# TUDSSL_condenar__Hardware_PCBs_Misc_Apo4.net
KiCad netlist of a schematic drawn in Altium Designer
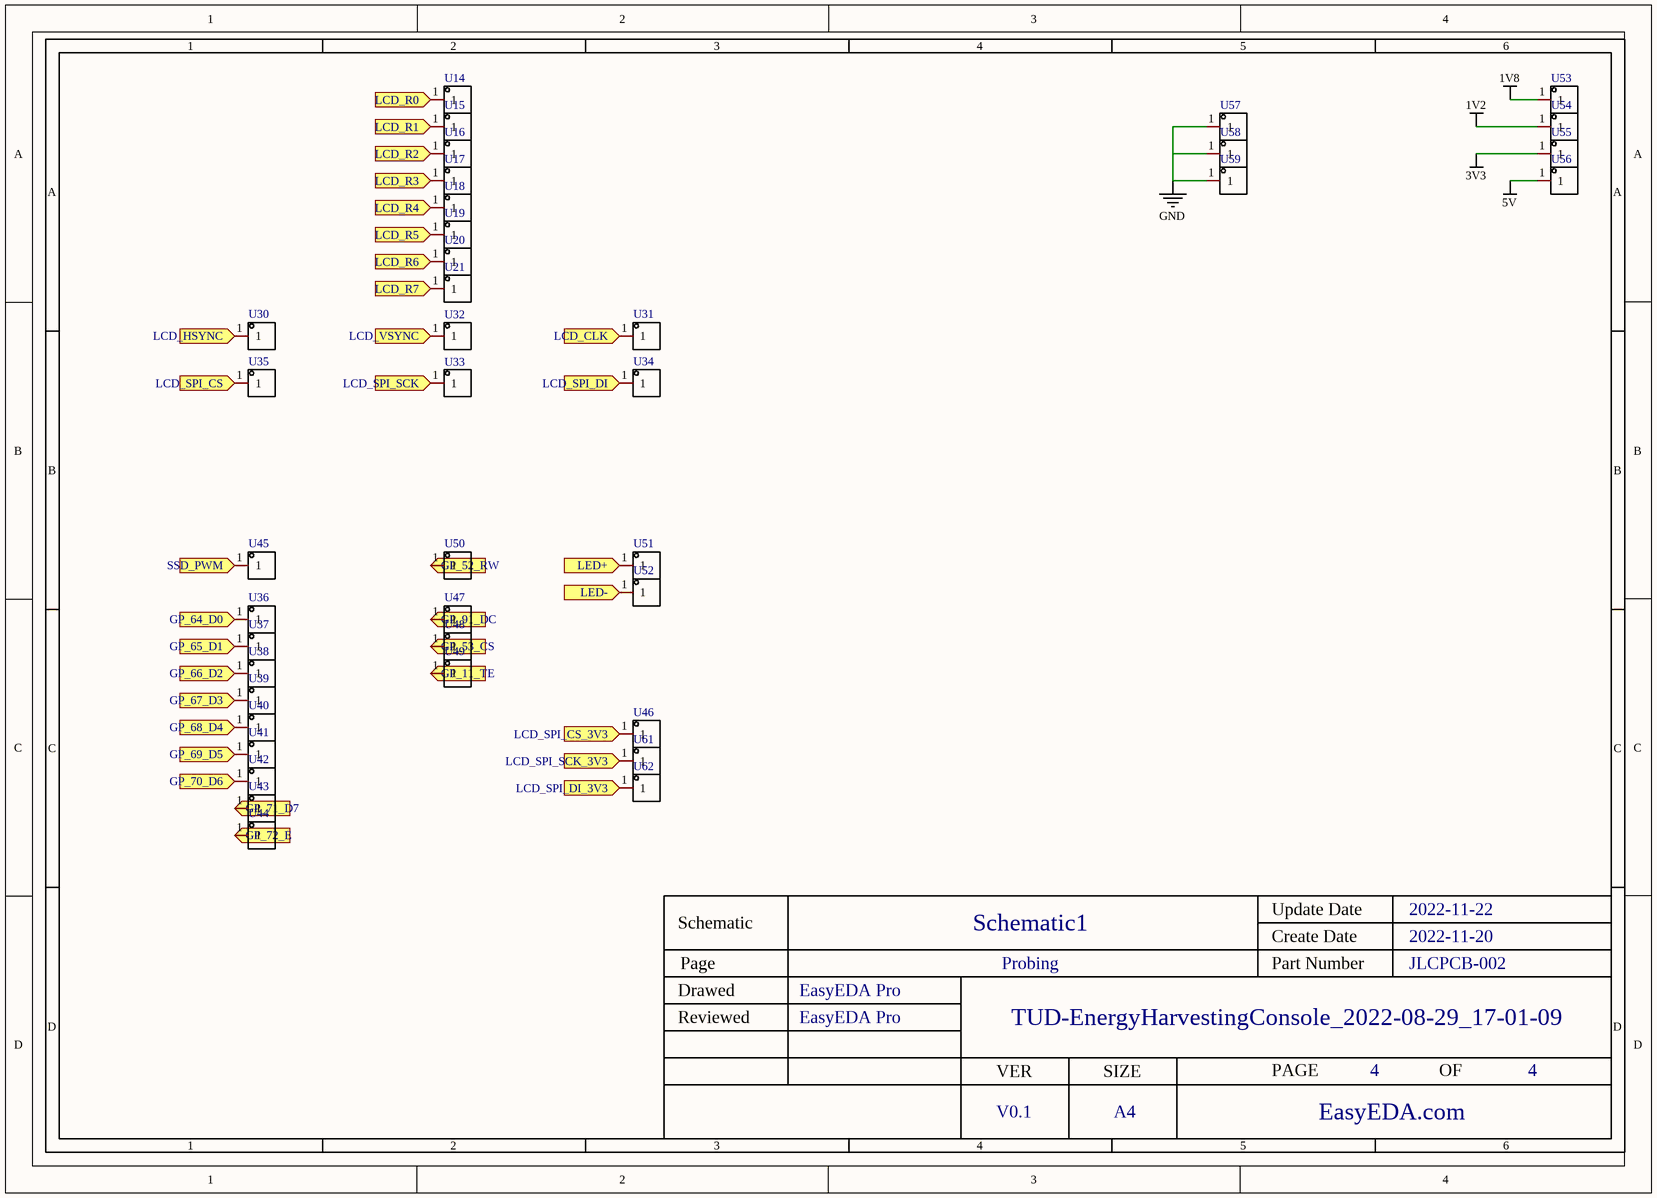
[diagram p0: TUDSSL_condenar__Hardware_PCBs_Misc_Apo4devkit2COM50_Schematic1__3_Probing.schdoc]

(export (version "E")
  (design (tool "Eeschema 10.0.6"))
  (components
    (comp (ref "U14")
      (value "5001_C238122")
      (fields (field (name "MANUFACTURER") "Keystone") (field (name "MANUFACTURER PART") "5001"))
      (libsource (lib "altium-import") (part "root_0_5001_C238122_"))
    )
    (comp (ref "U15")
      (value "5001_C238122")
      (fields (field (name "MANUFACTURER") "Keystone") (field (name "MANUFACTURER PART") "5001"))
      (libsource (lib "altium-import") (part "root_0_5001_C238122_"))
    )
    (comp (ref "U16")
      (value "5001_C238122")
      (fields (field (name "MANUFACTURER") "Keystone") (field (name "MANUFACTURER PART") "5001"))
      (libsource (lib "altium-import") (part "root_0_5001_C238122_"))
    )
    (comp (ref "U17")
      (value "5001_C238122")
      (fields (field (name "MANUFACTURER") "Keystone") (field (name "MANUFACTURER PART") "5001"))
      (libsource (lib "altium-import") (part "root_0_5001_C238122_"))
    )
    (comp (ref "U18")
      (value "5001_C238122")
      (fields (field (name "MANUFACTURER") "Keystone") (field (name "MANUFACTURER PART") "5001"))
      (libsource (lib "altium-import") (part "root_0_5001_C238122_"))
    )
    (comp (ref "U19")
      (value "5001_C238122")
      (fields (field (name "MANUFACTURER") "Keystone") (field (name "MANUFACTURER PART") "5001"))
      (libsource (lib "altium-import") (part "root_0_5001_C238122_"))
    )
    (comp (ref "U20")
      (value "5001_C238122")
      (fields (field (name "MANUFACTURER") "Keystone") (field (name "MANUFACTURER PART") "5001"))
      (libsource (lib "altium-import") (part "root_0_5001_C238122_"))
    )
    (comp (ref "U21")
      (value "5001_C238122")
      (fields (field (name "MANUFACTURER") "Keystone") (field (name "MANUFACTURER PART") "5001"))
      (libsource (lib "altium-import") (part "root_0_5001_C238122_"))
    )
    (comp (ref "U30")
      (value "5001_C238122")
      (fields (field (name "MANUFACTURER") "Keystone") (field (name "MANUFACTURER PART") "5001"))
      (libsource (lib "altium-import") (part "root_0_5001_C238122_"))
    )
    (comp (ref "U31")
      (value "5001_C238122")
      (fields (field (name "MANUFACTURER") "Keystone") (field (name "MANUFACTURER PART") "5001"))
      (libsource (lib "altium-import") (part "root_0_5001_C238122_"))
    )
    (comp (ref "U32")
      (value "5001_C238122")
      (fields (field (name "MANUFACTURER") "Keystone") (field (name "MANUFACTURER PART") "5001"))
      (libsource (lib "altium-import") (part "root_0_5001_C238122_"))
    )
    (comp (ref "U33")
      (value "5001_C238122")
      (fields (field (name "MANUFACTURER") "Keystone") (field (name "MANUFACTURER PART") "5001"))
      (libsource (lib "altium-import") (part "root_0_5001_C238122_"))
    )
    (comp (ref "U34")
      (value "5001_C238122")
      (fields (field (name "MANUFACTURER") "Keystone") (field (name "MANUFACTURER PART") "5001"))
      (libsource (lib "altium-import") (part "root_0_5001_C238122_"))
    )
    (comp (ref "U35")
      (value "5001_C238122")
      (fields (field (name "MANUFACTURER") "Keystone") (field (name "MANUFACTURER PART") "5001"))
      (libsource (lib "altium-import") (part "root_0_5001_C238122_"))
    )
    (comp (ref "U36")
      (value "5001_C238122")
      (fields (field (name "MANUFACTURER") "Keystone") (field (name "MANUFACTURER PART") "5001"))
      (libsource (lib "altium-import") (part "root_0_5001_C238122_"))
    )
    (comp (ref "U37")
      (value "5001_C238122")
      (fields (field (name "MANUFACTURER") "Keystone") (field (name "MANUFACTURER PART") "5001"))
      (libsource (lib "altium-import") (part "root_0_5001_C238122_"))
    )
    (comp (ref "U38")
      (value "5001_C238122")
      (fields (field (name "MANUFACTURER") "Keystone") (field (name "MANUFACTURER PART") "5001"))
      (libsource (lib "altium-import") (part "root_0_5001_C238122_"))
    )
    (comp (ref "U39")
      (value "5001_C238122")
      (fields (field (name "MANUFACTURER") "Keystone") (field (name "MANUFACTURER PART") "5001"))
      (libsource (lib "altium-import") (part "root_0_5001_C238122_"))
    )
    (comp (ref "U40")
      (value "5001_C238122")
      (fields (field (name "MANUFACTURER") "Keystone") (field (name "MANUFACTURER PART") "5001"))
      (libsource (lib "altium-import") (part "root_0_5001_C238122_"))
    )
    (comp (ref "U41")
      (value "5001_C238122")
      (fields (field (name "MANUFACTURER") "Keystone") (field (name "MANUFACTURER PART") "5001"))
      (libsource (lib "altium-import") (part "root_0_5001_C238122_"))
    )
    (comp (ref "U42")
      (value "5001_C238122")
      (fields (field (name "MANUFACTURER") "Keystone") (field (name "MANUFACTURER PART") "5001"))
      (libsource (lib "altium-import") (part "root_0_5001_C238122_"))
    )
    (comp (ref "U43")
      (value "5001_C238122")
      (fields (field (name "MANUFACTURER") "Keystone") (field (name "MANUFACTURER PART") "5001"))
      (libsource (lib "altium-import") (part "root_0_5001_C238122_"))
    )
    (comp (ref "U44")
      (value "5001_C238122")
      (fields (field (name "MANUFACTURER") "Keystone") (field (name "MANUFACTURER PART") "5001"))
      (libsource (lib "altium-import") (part "root_0_5001_C238122_"))
    )
    (comp (ref "U45")
      (value "5001_C238122")
      (fields (field (name "MANUFACTURER") "Keystone") (field (name "MANUFACTURER PART") "5001"))
      (libsource (lib "altium-import") (part "root_0_5001_C238122_"))
    )
    (comp (ref "U46")
      (value "5001_C238122")
      (fields (field (name "MANUFACTURER") "Keystone") (field (name "MANUFACTURER PART") "5001"))
      (libsource (lib "altium-import") (part "root_0_5001_C238122_"))
    )
    (comp (ref "U47")
      (value "5001_C238122")
      (fields (field (name "MANUFACTURER") "Keystone") (field (name "MANUFACTURER PART") "5001"))
      (libsource (lib "altium-import") (part "root_0_5001_C238122_"))
    )
    (comp (ref "U48")
      (value "5001_C238122")
      (fields (field (name "MANUFACTURER") "Keystone") (field (name "MANUFACTURER PART") "5001"))
      (libsource (lib "altium-import") (part "root_0_5001_C238122_"))
    )
    (comp (ref "U49")
      (value "5001_C238122")
      (fields (field (name "MANUFACTURER") "Keystone") (field (name "MANUFACTURER PART") "5001"))
      (libsource (lib "altium-import") (part "root_0_5001_C238122_"))
    )
    (comp (ref "U50")
      (value "5001_C238122")
      (fields (field (name "MANUFACTURER") "Keystone") (field (name "MANUFACTURER PART") "5001"))
      (libsource (lib "altium-import") (part "root_0_5001_C238122_"))
    )
    (comp (ref "U51")
      (value "5001_C238122")
      (fields (field (name "MANUFACTURER") "Keystone") (field (name "MANUFACTURER PART") "5001"))
      (libsource (lib "altium-import") (part "root_0_5001_C238122_"))
    )
    (comp (ref "U52")
      (value "5001_C238122")
      (fields (field (name "MANUFACTURER") "Keystone") (field (name "MANUFACTURER PART") "5001"))
      (libsource (lib "altium-import") (part "root_0_5001_C238122_"))
    )
    (comp (ref "U53")
      (value "5001_C238122")
      (fields (field (name "MANUFACTURER") "Keystone") (field (name "MANUFACTURER PART") "5001"))
      (libsource (lib "altium-import") (part "root_0_5001_C238122_"))
    )
    (comp (ref "U54")
      (value "5001_C238122")
      (fields (field (name "MANUFACTURER") "Keystone") (field (name "MANUFACTURER PART") "5001"))
      (libsource (lib "altium-import") (part "root_0_5001_C238122_"))
    )
    (comp (ref "U55")
      (value "5001_C238122")
      (fields (field (name "MANUFACTURER") "Keystone") (field (name "MANUFACTURER PART") "5001"))
      (libsource (lib "altium-import") (part "root_0_5001_C238122_"))
    )
    (comp (ref "U56")
      (value "5001_C238122")
      (fields (field (name "MANUFACTURER") "Keystone") (field (name "MANUFACTURER PART") "5001"))
      (libsource (lib "altium-import") (part "root_0_5001_C238122_"))
    )
    (comp (ref "U57")
      (value "5001_C238122")
      (fields (field (name "MANUFACTURER") "Keystone") (field (name "MANUFACTURER PART") "5001"))
      (libsource (lib "altium-import") (part "root_0_5001_C238122_"))
    )
    (comp (ref "U58")
      (value "5001_C238122")
      (fields (field (name "MANUFACTURER") "Keystone") (field (name "MANUFACTURER PART") "5001"))
      (libsource (lib "altium-import") (part "root_0_5001_C238122_"))
    )
    (comp (ref "U59")
      (value "5001_C238122")
      (fields (field (name "MANUFACTURER") "Keystone") (field (name "MANUFACTURER PART") "5001"))
      (libsource (lib "altium-import") (part "root_0_5001_C238122_"))
    )
    (comp (ref "U61")
      (value "5001_C238122")
      (fields (field (name "MANUFACTURER") "Keystone") (field (name "MANUFACTURER PART") "5001"))
      (libsource (lib "altium-import") (part "root_0_5001_C238122_"))
    )
    (comp (ref "U62")
      (value "5001_C238122")
      (fields (field (name "MANUFACTURER") "Keystone") (field (name "MANUFACTURER PART") "5001"))
      (libsource (lib "altium-import") (part "root_0_5001_C238122_"))
    )
  )
  (nets
    (net (code "1") (name "/GP_11_TE") (class "Default")
      (node (ref "U49") (pin "1") (pinfunction "1_1") (pintype "passive"))
    )
    (net (code "2") (name "/GP_52_RW") (class "Default")
      (node (ref "U50") (pin "1") (pinfunction "1_1") (pintype "passive"))
    )
    (net (code "3") (name "/GP_53_CS") (class "Default")
      (node (ref "U48") (pin "1") (pinfunction "1_1") (pintype "passive"))
    )
    (net (code "4") (name "/GP_64_D0") (class "Default")
      (node (ref "U36") (pin "1") (pinfunction "1_1") (pintype "passive"))
    )
    (net (code "5") (name "/GP_65_D1") (class "Default")
      (node (ref "U37") (pin "1") (pinfunction "1_1") (pintype "passive"))
    )
    (net (code "6") (name "/GP_66_D2") (class "Default")
      (node (ref "U38") (pin "1") (pinfunction "1_1") (pintype "passive"))
    )
    (net (code "7") (name "/GP_67_D3") (class "Default")
      (node (ref "U39") (pin "1") (pinfunction "1_1") (pintype "passive"))
    )
    (net (code "8") (name "/GP_68_D4") (class "Default")
      (node (ref "U40") (pin "1") (pinfunction "1_1") (pintype "passive"))
    )
    (net (code "9") (name "/GP_69_D5") (class "Default")
      (node (ref "U41") (pin "1") (pinfunction "1_1") (pintype "passive"))
    )
    (net (code "10") (name "/GP_70_D6") (class "Default")
      (node (ref "U42") (pin "1") (pinfunction "1_1") (pintype "passive"))
    )
    (net (code "11") (name "/GP_71_D7") (class "Default")
      (node (ref "U43") (pin "1") (pinfunction "1_1") (pintype "passive"))
    )
    (net (code "12") (name "/GP_72_E") (class "Default")
      (node (ref "U44") (pin "1") (pinfunction "1_1") (pintype "passive"))
    )
    (net (code "13") (name "/GP_91_DC") (class "Default")
      (node (ref "U47") (pin "1") (pinfunction "1_1") (pintype "passive"))
    )
    (net (code "14") (name "/LCD_CLK") (class "Default")
      (node (ref "U31") (pin "1") (pinfunction "1_1") (pintype "passive"))
    )
    (net (code "15") (name "/LCD_HSYNC") (class "Default")
      (node (ref "U30") (pin "1") (pinfunction "1_1") (pintype "passive"))
    )
    (net (code "16") (name "/LCD_R0") (class "Default")
      (node (ref "U14") (pin "1") (pinfunction "1_1") (pintype "passive"))
    )
    (net (code "17") (name "/LCD_R1") (class "Default")
      (node (ref "U15") (pin "1") (pinfunction "1_1") (pintype "passive"))
    )
    (net (code "18") (name "/LCD_R2") (class "Default")
      (node (ref "U16") (pin "1") (pinfunction "1_1") (pintype "passive"))
    )
    (net (code "19") (name "/LCD_R3") (class "Default")
      (node (ref "U17") (pin "1") (pinfunction "1_1") (pintype "passive"))
    )
    (net (code "20") (name "/LCD_R4") (class "Default")
      (node (ref "U18") (pin "1") (pinfunction "1_1") (pintype "passive"))
    )
    (net (code "21") (name "/LCD_R5") (class "Default")
      (node (ref "U19") (pin "1") (pinfunction "1_1") (pintype "passive"))
    )
    (net (code "22") (name "/LCD_R6") (class "Default")
      (node (ref "U20") (pin "1") (pinfunction "1_1") (pintype "passive"))
    )
    (net (code "23") (name "/LCD_R7") (class "Default")
      (node (ref "U21") (pin "1") (pinfunction "1_1") (pintype "passive"))
    )
    (net (code "24") (name "/LCD_SPI_CS") (class "Default")
      (node (ref "U35") (pin "1") (pinfunction "1_1") (pintype "passive"))
    )
    (net (code "25") (name "/LCD_SPI_CS_3V3") (class "Default")
      (node (ref "U46") (pin "1") (pinfunction "1_1") (pintype "passive"))
    )
    (net (code "26") (name "/LCD_SPI_DI") (class "Default")
      (node (ref "U34") (pin "1") (pinfunction "1_1") (pintype "passive"))
    )
    (net (code "27") (name "/LCD_SPI_DI_3V3") (class "Default")
      (node (ref "U62") (pin "1") (pinfunction "1_1") (pintype "passive"))
    )
    (net (code "28") (name "/LCD_SPI_SCK") (class "Default")
      (node (ref "U33") (pin "1") (pinfunction "1_1") (pintype "passive"))
    )
    (net (code "29") (name "/LCD_SPI_SCK_3V3") (class "Default")
      (node (ref "U61") (pin "1") (pinfunction "1_1") (pintype "passive"))
    )
    (net (code "30") (name "/LCD_VSYNC") (class "Default")
      (node (ref "U32") (pin "1") (pinfunction "1_1") (pintype "passive"))
    )
    (net (code "31") (name "/LED+") (class "Default")
      (node (ref "U51") (pin "1") (pinfunction "1_1") (pintype "passive"))
    )
    (net (code "32") (name "/LED-") (class "Default")
      (node (ref "U52") (pin "1") (pinfunction "1_1") (pintype "passive"))
    )
    (net (code "33") (name "/SSD_PWM") (class "Default")
      (node (ref "U45") (pin "1") (pinfunction "1_1") (pintype "passive"))
    )
    (net (code "34") (name "1V2") (class "Default")
      (node (ref "U54") (pin "1") (pinfunction "1_1") (pintype "passive"))
    )
    (net (code "35") (name "1V8") (class "Default")
      (node (ref "U53") (pin "1") (pinfunction "1_1") (pintype "passive"))
    )
    (net (code "36") (name "3V3") (class "Default")
      (node (ref "U55") (pin "1") (pinfunction "1_1") (pintype "passive"))
    )
    (net (code "37") (name "5V") (class "Default")
      (node (ref "U56") (pin "1") (pinfunction "1_1") (pintype "passive"))
    )
    (net (code "38") (name "GND") (class "Default")
      (node (ref "U57") (pin "1") (pinfunction "1_1") (pintype "passive"))
      (node (ref "U58") (pin "1") (pinfunction "1_1") (pintype "passive"))
      (node (ref "U59") (pin "1") (pinfunction "1_1") (pintype "passive"))
    )
  )
)
